# CONN.net
KiCad netlist of a schematic drawn in Altium Designer
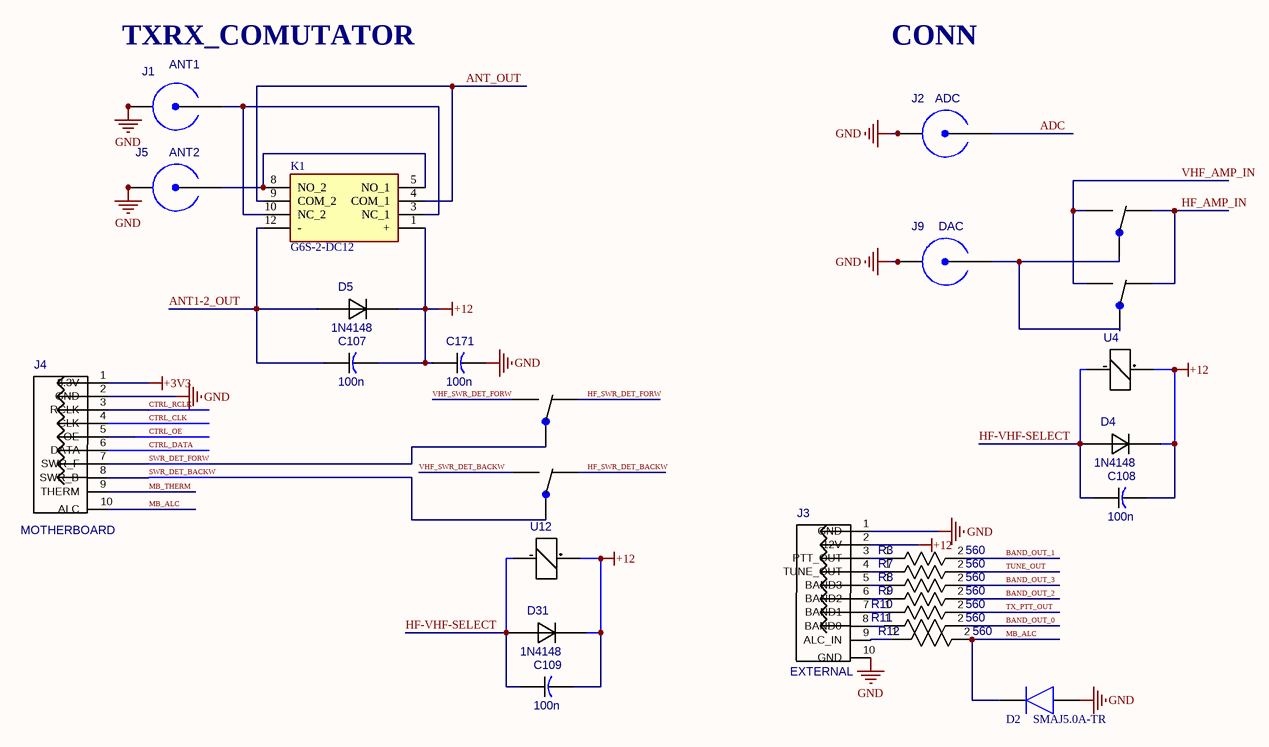
[diagram p0: CONN.SchDoc]

(export (version "E")
  (design (tool "Eeschema 10.0.6"))
  (components
    (comp (ref "C107")
      (value "100n")
      (footprint "CAP_0805")
      (description "CAP_0805")
      (libsource (lib "*") (part "CAP_0805"))
    )
    (comp (ref "C108")
      (value "100n")
      (footprint "CAP_0805")
      (description "CAP_0805")
      (libsource (lib "*") (part "CAP_0805"))
    )
    (comp (ref "C109")
      (value "100n")
      (footprint "CAP_0805")
      (description "CAP_0805")
      (libsource (lib "*") (part "CAP_0805"))
    )
    (comp (ref "C171")
      (value "100n")
      (footprint "CAP_0805")
      (description "CAP_0805")
      (libsource (lib "*") (part "CAP_0805"))
    )
    (comp (ref "D2")
      (value "SMAJ5.0A-TR")
      (footprint "SMBJ36CATR")
      (description "Diode")
      (fields
        (field (name "MANUFACTURER_PART_NUMBER") "SMLVT3V3")
        (field (name "MOUSER PART NUMBER") "511-SMLVT3V3")
      )
      (libsource (lib "RF-UNIT-BIG") (part "SMLVT3V3"))
    )
    (comp (ref "D4") (value "1N4148") (footprint "SS14") (libsource (lib "RF-UNIT-BIG") (part "1N4148")))
    (comp (ref "D5") (value "1N4148") (footprint "SS14") (libsource (lib "RF-UNIT-BIG") (part "1N4148")))
    (comp (ref "D31") (value "1N4148") (footprint "SS14") (libsource (lib "RF-UNIT-BIG") (part "1N4148")))
    (comp (ref "J1")
      (value "ANT1")
      (footprint "31-5431")
      (description "SMA")
      (libsource (lib "RF-UNIT_1") (part "31-5431"))
    )
    (comp (ref "J2")
      (value "ADC")
      (footprint "31-5431")
      (description "SMA")
      (libsource (lib "RF-UNIT_1") (part "31-5431"))
    )
    (comp (ref "J3")
      (value "EXTERNAL")
      (footprint "90131-0126")
      (description "2*5 PIN")
      (libsource (lib "RF-UNIT") (part "90131-0126"))
    )
    (comp (ref "J4")
      (value "MOTHERBOARD")
      (footprint "90131-0126")
      (description "2*5 PIN")
      (libsource (lib "RF-UNIT") (part "90131-0126"))
    )
    (comp (ref "J5")
      (value "ANT2")
      (footprint "31-5431")
      (description "SMA")
      (libsource (lib "RF-UNIT_1") (part "31-5431"))
    )
    (comp (ref "J9")
      (value "DAC")
      (footprint "31-5431")
      (description "SMA")
      (libsource (lib "RF-UNIT_1") (part "31-5431"))
    )
    (comp (ref "K1")
      (value "G6S-2-DC12")
      (footprint "SamacSys:G6S2DC12")
      (description "Relay or Contactor")
      (fields (field (name "MOUSER PART NUMBER") "653-G6S-2-DC12A"))
      (libsource (lib "*") (part "G6S-2-DC12"))
    )
    (comp (ref "R3")
      (value "560")
      (footprint "RES_0805")
      (description "RES_0805")
      (libsource (lib "*") (part "RES_0805"))
    )
    (comp (ref "R7")
      (value "560")
      (footprint "RES_0805")
      (description "RES_0805")
      (libsource (lib "*") (part "RES_0805"))
    )
    (comp (ref "R8")
      (value "560")
      (footprint "RES_0805")
      (description "RES_0805")
      (libsource (lib "*") (part "RES_0805"))
    )
    (comp (ref "R9")
      (value "560")
      (footprint "RES_0805")
      (description "RES_0805")
      (libsource (lib "*") (part "RES_0805"))
    )
    (comp (ref "R10")
      (value "560")
      (footprint "RES_0805")
      (description "RES_0805")
      (libsource (lib "*") (part "RES_0805"))
    )
    (comp (ref "R11")
      (value "560")
      (footprint "RES_0805")
      (description "RES_0805")
      (libsource (lib "*") (part "RES_0805"))
    )
    (comp (ref "R12")
      (value "560")
      (footprint "RES_0805")
      (description "RES_0805")
      (libsource (lib "*") (part "RES_0805"))
    )
    (comp (ref "U4")
      (value "Axicom IM06")
      (footprint "IM06GR")
      (libsource (lib "RF-UNIT-BIG") (part "Axicom IM06"))
    )
    (comp (ref "U12")
      (value "Axicom IM06")
      (footprint "IM06GR")
      (libsource (lib "RF-UNIT-BIG") (part "Axicom IM06"))
    )
  )
  (nets
    (net (code "1") (name "+3V3") (class "Default")
      (node (ref "J4") (pin "1") (pinfunction "3.3V_1") (pintype "passive"))
    )
    (net (code "2") (name "+12") (class "Default")
      (node (ref "C107") (pin "2") (pinfunction "2_2") (pintype "passive"))
      (node (ref "C108") (pin "2") (pinfunction "2_2") (pintype "passive"))
      (node (ref "C109") (pin "2") (pinfunction "2_2") (pintype "passive"))
      (node (ref "C171") (pin "1") (pinfunction "1_1") (pintype "passive"))
      (node (ref "D31") (pin "1") (pinfunction "K_1") (pintype "passive"))
      (node (ref "D4") (pin "1") (pinfunction "K_1") (pintype "passive"))
      (node (ref "D5") (pin "1") (pinfunction "K_1") (pintype "passive"))
      (node (ref "J3") (pin "2") (pinfunction "GND_2") (pintype "passive"))
      (node (ref "K1") (pin "1") (pinfunction "+_1") (pintype "passive"))
      (node (ref "U12") (pin "1") (pinfunction "+_1") (pintype "passive"))
      (node (ref "U4") (pin "1") (pinfunction "+_1") (pintype "passive"))
    )
    (net (code "4") (name "/ADC") (class "Default")
      (node (ref "J2") (pin "5") (pinfunction "CON_5") (pintype "passive"))
    )
    (net (code "5") (name "/ANT1-2_OUT") (class "Default")
      (node (ref "C107") (pin "1") (pinfunction "1_1") (pintype "passive"))
      (node (ref "D5") (pin "2") (pinfunction "A_2") (pintype "passive"))
      (node (ref "K1") (pin "12") (pinfunction "-_12") (pintype "passive"))
    )
    (net (code "6") (name "/ANT_OUT") (class "Default")
      (node (ref "K1") (pin "4") (pinfunction "COM_1_4") (pintype "passive"))
      (node (ref "K1") (pin "9") (pinfunction "COM_2_9") (pintype "passive"))
    )
    (net (code "7") (name "/BAND_OUT_0") (class "Default")
      (node (ref "R11") (pin "2") (pinfunction "2_2") (pintype "passive"))
    )
    (net (code "8") (name "/BAND_OUT_1") (class "Default")
      (node (ref "R3") (pin "2") (pinfunction "2_2") (pintype "passive"))
    )
    (net (code "9") (name "/BAND_OUT_2") (class "Default")
      (node (ref "R9") (pin "2") (pinfunction "2_2") (pintype "passive"))
    )
    (net (code "10") (name "/BAND_OUT_3") (class "Default")
      (node (ref "R8") (pin "2") (pinfunction "2_2") (pintype "passive"))
    )
    (net (code "11") (name "/CTRL_CLK") (class "Default")
      (node (ref "J4") (pin "4") (pinfunction "CLK_4") (pintype "passive"))
    )
    (net (code "12") (name "/CTRL_DATA") (class "Default")
      (node (ref "J4") (pin "6") (pinfunction "DATA_6") (pintype "passive"))
    )
    (net (code "13") (name "/CTRL_OE") (class "Default")
      (node (ref "J4") (pin "5") (pinfunction "OE_5") (pintype "passive"))
    )
    (net (code "14") (name "/CTRL_RCLK") (class "Default")
      (node (ref "J4") (pin "3") (pinfunction "RCLK_3") (pintype "passive"))
    )
    (net (code "15") (name "/HF-VHF-SELECT") (class "Default")
      (node (ref "C108") (pin "1") (pinfunction "1_1") (pintype "passive"))
      (node (ref "C109") (pin "1") (pinfunction "1_1") (pintype "passive"))
      (node (ref "D31") (pin "2") (pinfunction "A_2") (pintype "passive"))
      (node (ref "D4") (pin "2") (pinfunction "A_2") (pintype "passive"))
      (node (ref "U12") (pin "8") (pinfunction "-_8") (pintype "passive"))
      (node (ref "U4") (pin "8") (pinfunction "-_8") (pintype "passive"))
    )
    (net (code "16") (name "/HF_AMP_IN") (class "Default")
      (node (ref "U4") (pin "2") (pinfunction "O_2") (pintype "passive"))
      (node (ref "U4") (pin "7") (pinfunction "O_7") (pintype "passive"))
    )
    (net (code "17") (name "/HF_SWR_DET_BACKW") (class "Default")
      (node (ref "U12") (pin "2") (pinfunction "O_2") (pintype "passive"))
    )
    (net (code "18") (name "/HF_SWR_DET_FORW") (class "Default")
      (node (ref "U12") (pin "7") (pinfunction "O_7") (pintype "passive"))
    )
    (net (code "19") (name "/MB_ALC") (class "Default")
      (node (ref "D2") (pin "1") (pinfunction "K_1") (pintype "passive"))
      (node (ref "J4") (pin "10") (pinfunction "ALC_10") (pintype "passive"))
      (node (ref "R12") (pin "2") (pinfunction "2_2") (pintype "passive"))
    )
    (net (code "20") (name "/MB_THERM") (class "Default")
      (node (ref "J4") (pin "9") (pinfunction "THERM_9") (pintype "passive"))
    )
    (net (code "21") (name "/SWR_DET_BACKW") (class "Default")
      (node (ref "J4") (pin "8") (pinfunction "SWR_B_8") (pintype "passive"))
      (node (ref "U12") (pin "3") (pinfunction "P_3") (pintype "passive"))
    )
    (net (code "22") (name "/SWR_DET_FORW") (class "Default")
      (node (ref "J4") (pin "7") (pinfunction "SWR_F_7") (pintype "passive"))
      (node (ref "U12") (pin "6") (pinfunction "P_6") (pintype "passive"))
    )
    (net (code "23") (name "/TUNE_OUT") (class "Default")
      (node (ref "R7") (pin "2") (pinfunction "2_2") (pintype "passive"))
    )
    (net (code "24") (name "/TX_PTT_OUT") (class "Default")
      (node (ref "R10") (pin "2") (pinfunction "2_2") (pintype "passive"))
    )
    (net (code "25") (name "/VHF_AMP_IN") (class "Default")
      (node (ref "U4") (pin "4") (pinfunction "S_4") (pintype "passive"))
      (node (ref "U4") (pin "5") (pinfunction "S_5") (pintype "passive"))
    )
    (net (code "26") (name "/VHF_SWR_DET_BACKW") (class "Default")
      (node (ref "U12") (pin "4") (pinfunction "S_4") (pintype "passive"))
    )
    (net (code "27") (name "/VHF_SWR_DET_FORW") (class "Default")
      (node (ref "U12") (pin "5") (pinfunction "S_5") (pintype "passive"))
    )
    (net (code "28") (name "GND") (class "Default")
      (node (ref "C171") (pin "2") (pinfunction "2_2") (pintype "passive"))
      (node (ref "D2") (pin "2") (pinfunction "A_2") (pintype "passive"))
      (node (ref "J1") (pin "1") (pinfunction "GND_1") (pintype "passive"))
      (node (ref "J1") (pin "2") (pinfunction "GND_2") (pintype "passive"))
      (node (ref "J1") (pin "3") (pinfunction "GND_3") (pintype "passive"))
      (node (ref "J1") (pin "4") (pinfunction "GND_4") (pintype "passive"))
      (node (ref "J2") (pin "1") (pinfunction "GND_1") (pintype "passive"))
      (node (ref "J2") (pin "2") (pinfunction "GND_2") (pintype "passive"))
      (node (ref "J2") (pin "3") (pinfunction "GND_3") (pintype "passive"))
      (node (ref "J2") (pin "4") (pinfunction "GND_4") (pintype "passive"))
      (node (ref "J3") (pin "1") (pinfunction "3.3V_1") (pintype "passive"))
      (node (ref "J3") (pin "10") (pinfunction "ALC_10") (pintype "passive"))
      (node (ref "J4") (pin "2") (pinfunction "GND_2") (pintype "passive"))
      (node (ref "J5") (pin "1") (pinfunction "GND_1") (pintype "passive"))
      (node (ref "J5") (pin "2") (pinfunction "GND_2") (pintype "passive"))
      (node (ref "J5") (pin "3") (pinfunction "GND_3") (pintype "passive"))
      (node (ref "J5") (pin "4") (pinfunction "GND_4") (pintype "passive"))
      (node (ref "J9") (pin "1") (pinfunction "GND_1") (pintype "passive"))
      (node (ref "J9") (pin "2") (pinfunction "GND_2") (pintype "passive"))
      (node (ref "J9") (pin "3") (pinfunction "GND_3") (pintype "passive"))
      (node (ref "J9") (pin "4") (pinfunction "GND_4") (pintype "passive"))
    )
    (net (code "29") (name "Net-(J1-CON)") (class "Default")
      (node (ref "J1") (pin "5") (pinfunction "CON_5") (pintype "passive"))
      (node (ref "K1") (pin "10") (pinfunction "NC_2_10") (pintype "passive"))
      (node (ref "K1") (pin "3") (pinfunction "NC_1_3") (pintype "passive"))
    )
    (net (code "30") (name "Net-(J3-CLK)") (class "Default")
      (node (ref "J3") (pin "4") (pinfunction "CLK_4") (pintype "passive"))
      (node (ref "R7") (pin "1") (pinfunction "1_1") (pintype "passive"))
    )
    (net (code "31") (name "Net-(J3-DATA)") (class "Default")
      (node (ref "J3") (pin "6") (pinfunction "DATA_6") (pintype "passive"))
      (node (ref "R9") (pin "1") (pinfunction "1_1") (pintype "passive"))
    )
    (net (code "32") (name "Net-(J3-OE)") (class "Default")
      (node (ref "J3") (pin "5") (pinfunction "OE_5") (pintype "passive"))
      (node (ref "R8") (pin "1") (pinfunction "1_1") (pintype "passive"))
    )
    (net (code "33") (name "Net-(J3-RCLK)") (class "Default")
      (node (ref "J3") (pin "3") (pinfunction "RCLK_3") (pintype "passive"))
      (node (ref "R3") (pin "1") (pinfunction "1_1") (pintype "passive"))
    )
    (net (code "34") (name "Net-(J3-SWR_B)") (class "Default")
      (node (ref "J3") (pin "8") (pinfunction "SWR_B_8") (pintype "passive"))
      (node (ref "R11") (pin "1") (pinfunction "1_1") (pintype "passive"))
    )
    (net (code "35") (name "Net-(J3-SWR_F)") (class "Default")
      (node (ref "J3") (pin "7") (pinfunction "SWR_F_7") (pintype "passive"))
      (node (ref "R10") (pin "1") (pinfunction "1_1") (pintype "passive"))
    )
    (net (code "36") (name "Net-(J3-THERM)") (class "Default")
      (node (ref "J3") (pin "9") (pinfunction "THERM_9") (pintype "passive"))
      (node (ref "R12") (pin "1") (pinfunction "1_1") (pintype "passive"))
    )
    (net (code "37") (name "Net-(J5-CON)") (class "Default")
      (node (ref "J5") (pin "5") (pinfunction "CON_5") (pintype "passive"))
      (node (ref "K1") (pin "5") (pinfunction "NO_1_5") (pintype "passive"))
      (node (ref "K1") (pin "8") (pinfunction "NO_2_8") (pintype "passive"))
    )
    (net (code "38") (name "Net-(J9-CON)") (class "Default")
      (node (ref "J9") (pin "5") (pinfunction "CON_5") (pintype "passive"))
      (node (ref "U4") (pin "3") (pinfunction "P_3") (pintype "passive"))
      (node (ref "U4") (pin "6") (pinfunction "P_6") (pintype "passive"))
    )
  )
)
